# GBE2_PHY.net
KiCad netlist of a schematic drawn in Altium Designer
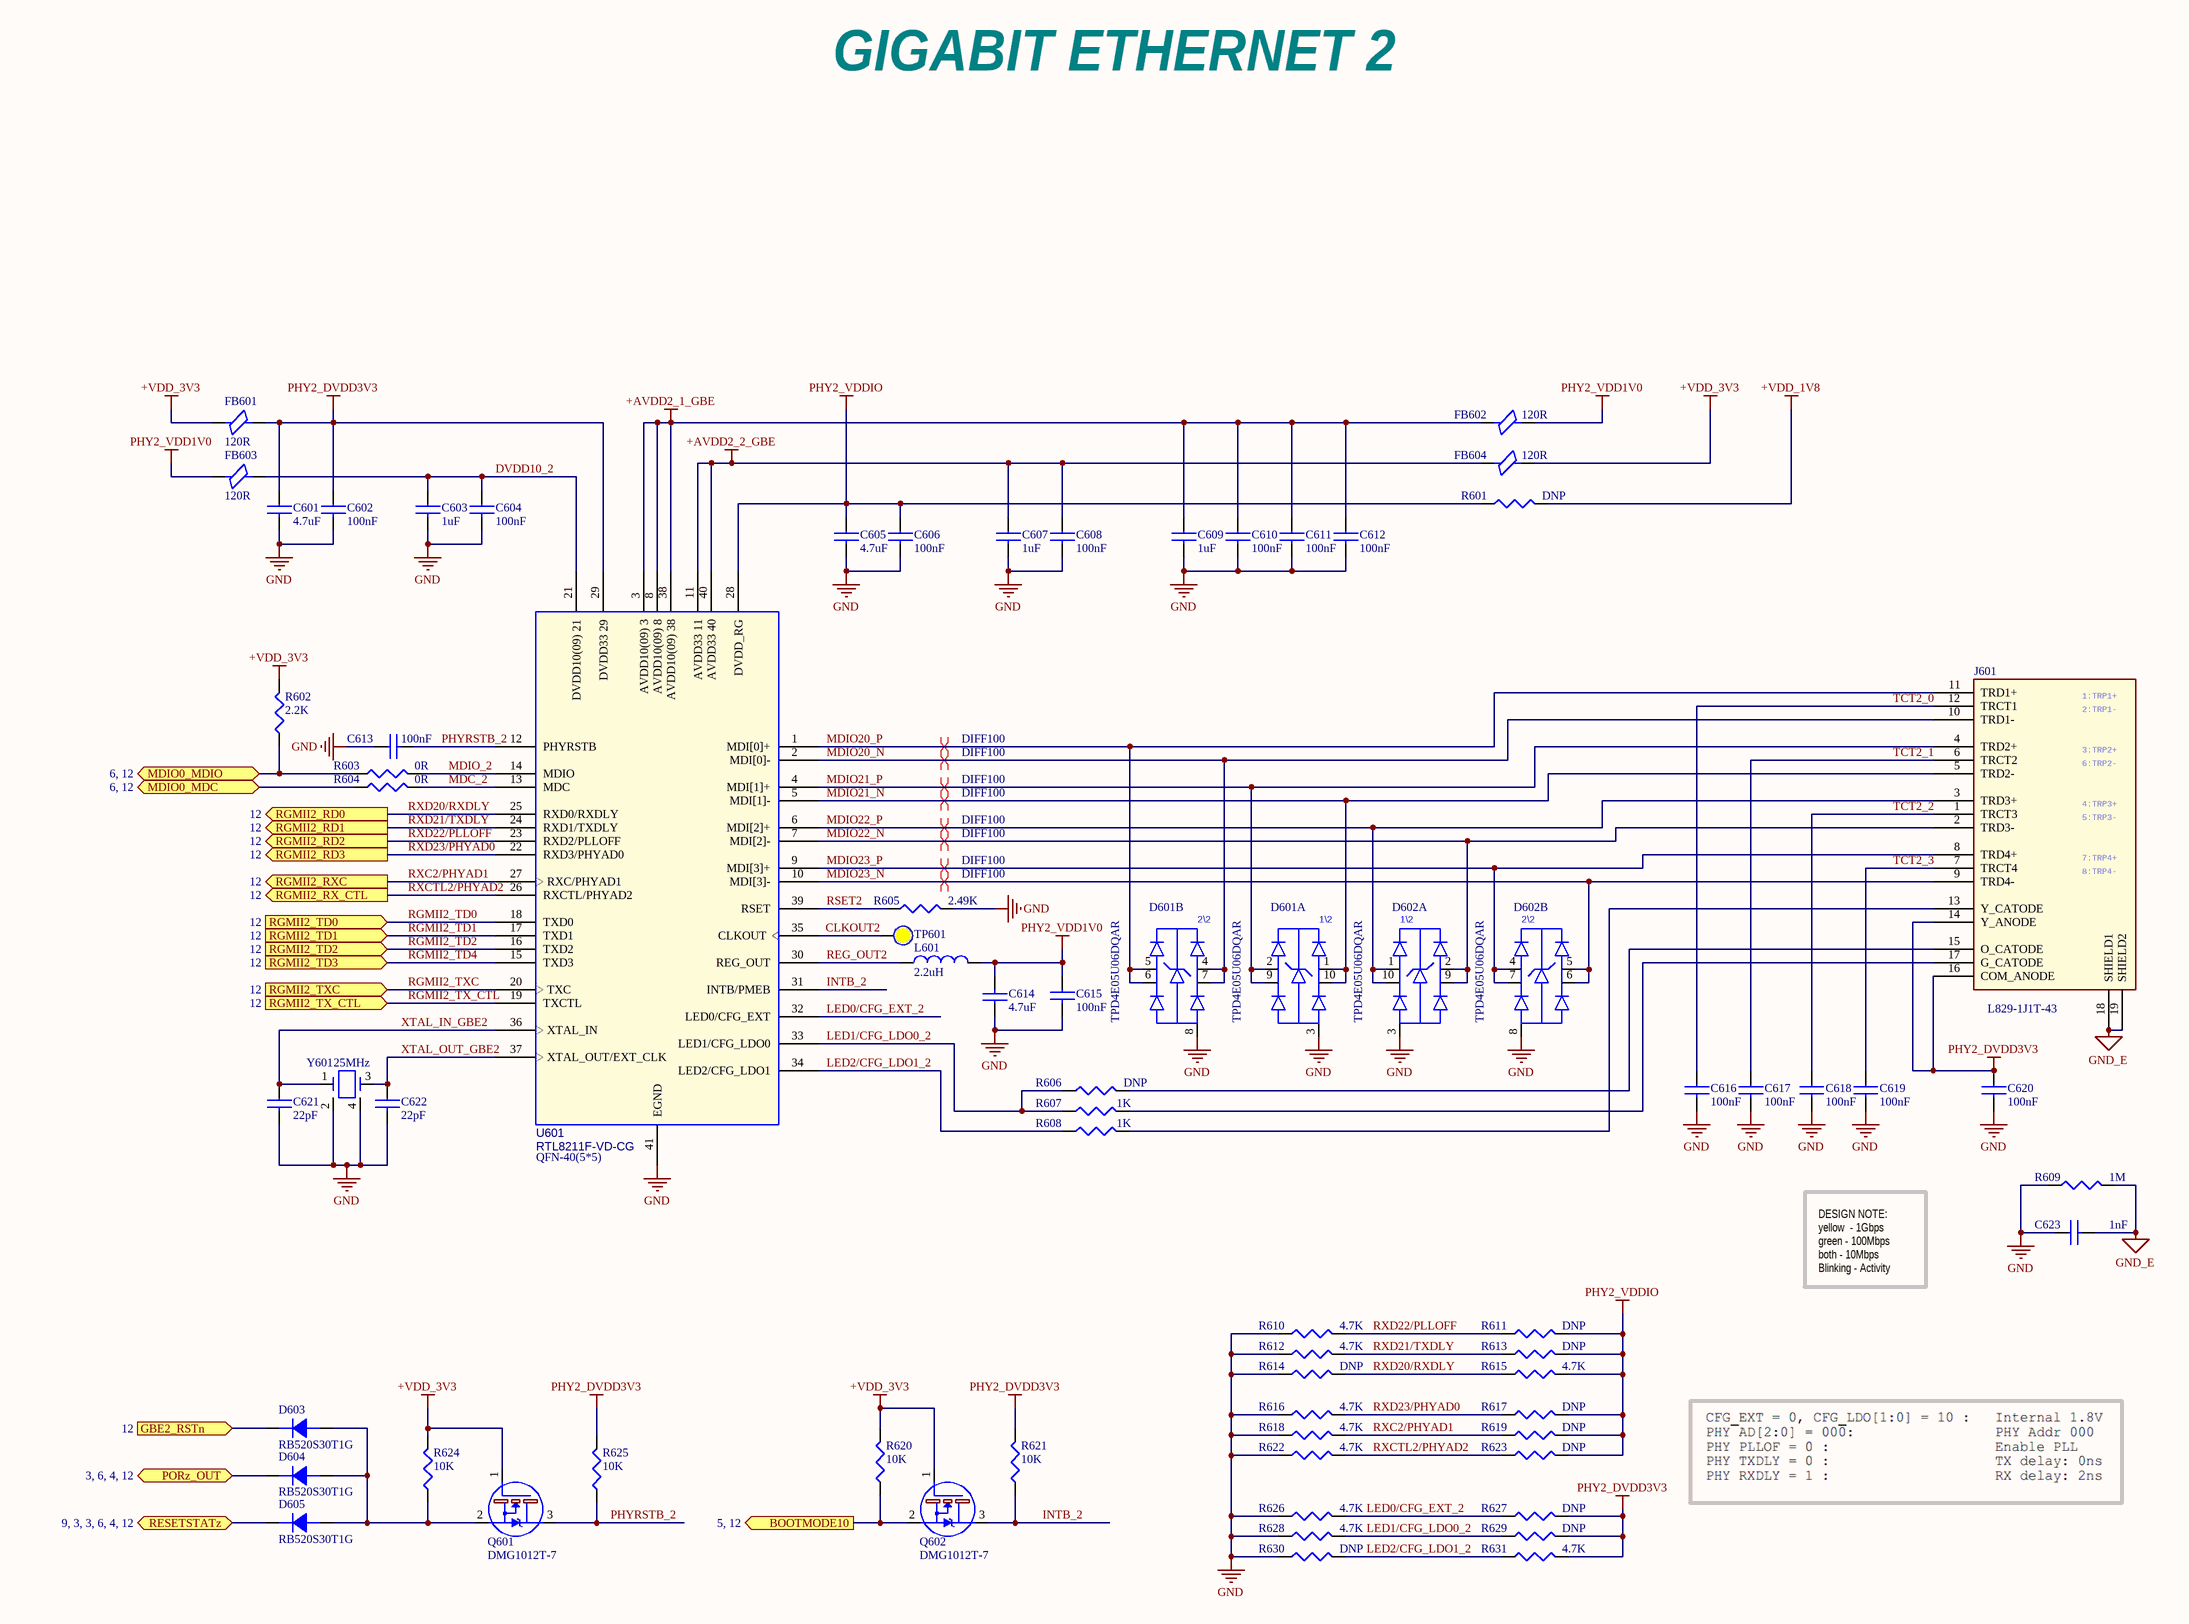
[diagram p0: GBE2 PHY.SchDoc]

(export (version "E")
  (design (tool "Eeschema 10.0.6"))
  (components
    (comp (ref "C601")
      (value "4.7uF")
      (footprint "C0402")
      (description "Multilayer Ceramic Capacitor, 4.7 uF, 6.3V, ± 10%, X5R, 0402 [1005 Metric]")
      (fields
        (field (name "MANUFACTURER") "Yageo")
        (field (name "MANUFACTURER PART NUMBER") "CC0402MRX5R5BB475")
      )
      (libsource (lib "Schlib SOM AM625") (part "CC0402MRX5R5BB475"))
    )
    (comp (ref "C602")
      (value "100nF")
      (footprint "C0201")
      (description "Multilayer Ceramic Capacitor, 0.1 uF, 16 V, ± 10%, X5R, 0201 [0603 Metric]")
      (fields
        (field (name "MANUFACTURER") "Yageo")
        (field (name "MANUFACTURER PART NUMBER") "CC0201KRX5R6BB104")
      )
      (libsource (lib "Schlib SOM AM625") (part "CC0201KRX5R6BB104"))
    )
    (comp (ref "C603")
      (value "1uF")
      (footprint "C0201")
      (description "Multilayer Ceramic Capacitor, 1 uF, 50 V, ± 0.1pF, C0G (NP0), 0201 [1005 Metric]")
      (fields
        (field (name "MANUFACTURER") "Yageo")
        (field (name "MANUFACTURER PART NUMBER") "CC0201MRX5R5BB105")
      )
      (libsource (lib "Schlib SOM AM625") (part "CC0201MRX5R5BB105"))
    )
    (comp (ref "C604")
      (value "100nF")
      (footprint "C0201")
      (description "Multilayer Ceramic Capacitor, 0.1 uF, 16 V, ± 10%, X5R, 0201 [0603 Metric]")
      (fields
        (field (name "MANUFACTURER") "Yageo")
        (field (name "MANUFACTURER PART NUMBER") "CC0201KRX5R6BB104")
      )
      (libsource (lib "Schlib SOM AM625") (part "CC0201KRX5R6BB104"))
    )
    (comp (ref "C605")
      (value "4.7uF")
      (footprint "C0402")
      (description "Multilayer Ceramic Capacitor, 4.7 uF, 6.3V, ± 10%, X5R, 0402 [1005 Metric]")
      (fields
        (field (name "MANUFACTURER") "Yageo")
        (field (name "MANUFACTURER PART NUMBER") "CC0402MRX5R5BB475")
      )
      (libsource (lib "Schlib SOM AM625") (part "CC0402MRX5R5BB475"))
    )
    (comp (ref "C606")
      (value "100nF")
      (footprint "C0201")
      (description "Multilayer Ceramic Capacitor, 0.1 uF, 16 V, ± 10%, X5R, 0201 [0603 Metric]")
      (fields
        (field (name "MANUFACTURER") "Yageo")
        (field (name "MANUFACTURER PART NUMBER") "CC0201KRX5R6BB104")
      )
      (libsource (lib "Schlib SOM AM625") (part "CC0201KRX5R6BB104"))
    )
    (comp (ref "C607")
      (value "1uF")
      (footprint "C0201")
      (description "Multilayer Ceramic Capacitor, 1 uF, 50 V, ± 0.1pF, C0G (NP0), 0201 [1005 Metric]")
      (fields
        (field (name "MANUFACTURER") "Yageo")
        (field (name "MANUFACTURER PART NUMBER") "CC0201MRX5R5BB105")
      )
      (libsource (lib "Schlib SOM AM625") (part "CC0201MRX5R5BB105"))
    )
    (comp (ref "C608")
      (value "100nF")
      (footprint "C0201")
      (description "Multilayer Ceramic Capacitor, 0.1 uF, 16 V, ± 10%, X5R, 0201 [0603 Metric]")
      (fields
        (field (name "MANUFACTURER") "Yageo")
        (field (name "MANUFACTURER PART NUMBER") "CC0201KRX5R6BB104")
      )
      (libsource (lib "Schlib SOM AM625") (part "CC0201KRX5R6BB104"))
    )
    (comp (ref "C609")
      (value "1uF")
      (footprint "C0201")
      (description "Multilayer Ceramic Capacitor, 1 uF, 50 V, ± 0.1pF, C0G (NP0), 0201 [1005 Metric]")
      (fields
        (field (name "MANUFACTURER") "Yageo")
        (field (name "MANUFACTURER PART NUMBER") "CC0201MRX5R5BB105")
      )
      (libsource (lib "Schlib SOM AM625") (part "CC0201MRX5R5BB105"))
    )
    (comp (ref "C610")
      (value "100nF")
      (footprint "C0201")
      (description "Multilayer Ceramic Capacitor, 0.1 uF, 16 V, ± 10%, X5R, 0201 [0603 Metric]")
      (fields
        (field (name "MANUFACTURER") "Yageo")
        (field (name "MANUFACTURER PART NUMBER") "CC0201KRX5R6BB104")
      )
      (libsource (lib "Schlib SOM AM625") (part "CC0201KRX5R6BB104"))
    )
    (comp (ref "C611")
      (value "100nF")
      (footprint "C0201")
      (description "Multilayer Ceramic Capacitor, 0.1 uF, 16 V, ± 10%, X5R, 0201 [0603 Metric]")
      (fields
        (field (name "MANUFACTURER") "Yageo")
        (field (name "MANUFACTURER PART NUMBER") "CC0201KRX5R6BB104")
      )
      (libsource (lib "Schlib SOM AM625") (part "CC0201KRX5R6BB104"))
    )
    (comp (ref "C612")
      (value "100nF")
      (footprint "C0201")
      (description "Multilayer Ceramic Capacitor, 0.1 uF, 16 V, ± 10%, X5R, 0201 [0603 Metric]")
      (fields
        (field (name "MANUFACTURER") "Yageo")
        (field (name "MANUFACTURER PART NUMBER") "CC0201KRX5R6BB104")
      )
      (libsource (lib "Schlib SOM AM625") (part "CC0201KRX5R6BB104"))
    )
    (comp (ref "C613")
      (value "100nF")
      (footprint "C0201")
      (description "Multilayer Ceramic Capacitor, 0.1 uF, 16 V, ± 10%, X5R, 0201 [0603 Metric]")
      (fields
        (field (name "MANUFACTURER") "Yageo")
        (field (name "MANUFACTURER PART NUMBER") "CC0201KRX5R6BB104")
      )
      (libsource (lib "Schlib SOM AM625") (part "CC0201KRX5R6BB104"))
    )
    (comp (ref "C614")
      (value "4.7uF")
      (footprint "C0402")
      (description "Multilayer Ceramic Capacitor, 4.7 uF, 6.3V, ± 10%, X5R, 0402 [1005 Metric]")
      (fields
        (field (name "MANUFACTURER") "Yageo")
        (field (name "MANUFACTURER PART NUMBER") "CC0402MRX5R5BB475")
      )
      (libsource (lib "Schlib SOM AM625") (part "CC0402MRX5R5BB475"))
    )
    (comp (ref "C615")
      (value "100nF")
      (footprint "C0201")
      (description "Multilayer Ceramic Capacitor, 0.1 uF, 16 V, ± 10%, X5R, 0201 [0603 Metric]")
      (fields
        (field (name "MANUFACTURER") "Yageo")
        (field (name "MANUFACTURER PART NUMBER") "CC0201KRX5R6BB104")
      )
      (libsource (lib "Schlib SOM AM625") (part "CC0201KRX5R6BB104"))
    )
    (comp (ref "C616")
      (value "100nF")
      (footprint "C0402")
      (description "Multilayer Ceramic Capacitor, 0.1 uF, 50 V, ± 10%, X5R, 0402 [1005 Metric]")
      (fields
        (field (name "MANUFACTURER") "TDK")
        (field (name "MANUFACTURER PART NUMBER") "C1005X5R1H104K050BB")
      )
      (libsource (lib "Schlib SOM AM625") (part "C1005X5R1H104K050BB"))
    )
    (comp (ref "C617")
      (value "100nF")
      (footprint "C0402")
      (description "Multilayer Ceramic Capacitor, 0.1 uF, 50 V, ± 10%, X5R, 0402 [1005 Metric]")
      (fields
        (field (name "MANUFACTURER") "TDK")
        (field (name "MANUFACTURER PART NUMBER") "C1005X5R1H104K050BB")
      )
      (libsource (lib "Schlib SOM AM625") (part "C1005X5R1H104K050BB"))
    )
    (comp (ref "C618")
      (value "100nF")
      (footprint "C0402")
      (description "Multilayer Ceramic Capacitor, 0.1 uF, 50 V, ± 10%, X5R, 0402 [1005 Metric]")
      (fields
        (field (name "MANUFACTURER") "TDK")
        (field (name "MANUFACTURER PART NUMBER") "C1005X5R1H104K050BB")
      )
      (libsource (lib "Schlib SOM AM625") (part "C1005X5R1H104K050BB"))
    )
    (comp (ref "C619")
      (value "100nF")
      (footprint "C0402")
      (description "Multilayer Ceramic Capacitor, 0.1 uF, 50 V, ± 10%, X5R, 0402 [1005 Metric]")
      (fields
        (field (name "MANUFACTURER") "TDK")
        (field (name "MANUFACTURER PART NUMBER") "C1005X5R1H104K050BB")
      )
      (libsource (lib "Schlib SOM AM625") (part "C1005X5R1H104K050BB"))
    )
    (comp (ref "C620")
      (value "100nF")
      (footprint "C0402")
      (description "Multilayer Ceramic Capacitor, 0.1 uF, 50 V, ± 10%, X5R, 0402 [1005 Metric]")
      (fields
        (field (name "MANUFACTURER") "TDK")
        (field (name "MANUFACTURER PART NUMBER") "C1005X5R1H104K050BB")
      )
      (libsource (lib "Schlib SOM AM625") (part "C1005X5R1H104K050BB"))
    )
    (comp (ref "C621")
      (value "22pF")
      (footprint "C0201")
      (description "0201 22 pF 50 V ±5 % Tolerance NP0 SMT Multilayer Ceramic Capacitor")
      (fields
        (field (name "MANUFACTURER") "Yageo")
        (field (name "MANUFACTURER PART NUMBER") "CC0201JRNPO9BN220")
      )
      (libsource (lib "Schlib SOM AM625") (part "CC0201JRNPO9BN220"))
    )
    (comp (ref "C622")
      (value "22pF")
      (footprint "C0201")
      (description "0201 22 pF 50 V ±5 % Tolerance NP0 SMT Multilayer Ceramic Capacitor")
      (fields
        (field (name "MANUFACTURER") "Yageo")
        (field (name "MANUFACTURER PART NUMBER") "CC0201JRNPO9BN220")
      )
      (libsource (lib "Schlib SOM AM625") (part "CC0201JRNPO9BN220"))
    )
    (comp (ref "C623")
      (value "1nF")
      (footprint "C1206B/3216MM")
      (description "Cap Ceramic 0.001uF 1000V X7R 10% Pad SMD 1206 125°C Low ESR Automotive Medical T/R")
      (fields
        (field (name "MANUFACTURER") "KEMET")
        (field (name "MANUFACTURER PART NUMBER") "C1206C102KDRACAUTO")
      )
      (libsource (lib "Schlib SOM AM625") (part "C1206C102KDRACAUTO"))
    )
    (comp (ref "D601")
      (value "TPD4E05U06DQAR")
      (footprint "10-USON")
      (description "Quad 0.5-pF, 5.5-V, ±12-kV ESD protection diode for USB, HDMI & High Speed Interfaces")
      (fields (field (name "MANUFACTURER") "Texas Instruments"))
      (libsource (lib "Schlib SOM AM625") (part "TPD4E05U06DQAR"))
    )
    (comp (ref "D602")
      (value "TPD4E05U06DQAR")
      (footprint "10-USON")
      (description "Quad 0.5-pF, 5.5-V, ±12-kV ESD protection diode for USB, HDMI & High Speed Interfaces")
      (fields (field (name "MANUFACTURER") "Texas Instruments"))
      (libsource (lib "Schlib SOM AM625") (part "TPD4E05U06DQAR"))
    )
    (comp (ref "D603")
      (value "RB520S30T1G")
      (footprint "sod_523")
      (description "Diode Schottky 30V 0.2A 2-Pin SOD-523 T/R - Product that comes on tape, but is not reeled")
      (fields (field (name "MANUFACTURER") "ON Semiconductor"))
      (libsource (lib "Schlib SOM AM625") (part "RB520S30T1G"))
    )
    (comp (ref "D604")
      (value "RB520S30T1G")
      (footprint "sod_523")
      (description "Diode Schottky 30V 0.2A 2-Pin SOD-523 T/R - Product that comes on tape, but is not reeled")
      (fields (field (name "MANUFACTURER") "ON Semiconductor"))
      (libsource (lib "Schlib SOM AM625") (part "RB520S30T1G"))
    )
    (comp (ref "D605")
      (value "RB520S30T1G")
      (footprint "sod_523")
      (description "Diode Schottky 30V 0.2A 2-Pin SOD-523 T/R - Product that comes on tape, but is not reeled")
      (fields (field (name "MANUFACTURER") "ON Semiconductor"))
      (libsource (lib "Schlib SOM AM625") (part "RB520S30T1G"))
    )
    (comp (ref "FB601")
      (value "120R")
      (footprint "FB0402")
      (description "Ferrite Beads Multi-Layer 120Ohm 25% 100MHz 1.3A 0.09Ohm DCR 0402 Automotive T/R")
      (fields
        (field (name "MANUFACTURER") "Murata")
        (field (name "MANUFACTURER PART NUMBER") "BLM15PD121SZ1D")
      )
      (libsource (lib "Schlib SOM AM625") (part "BLM15PD121SZ1D"))
    )
    (comp (ref "FB602")
      (value "120R")
      (footprint "FB0402")
      (description "Ferrite Beads Multi-Layer 120Ohm 25% 100MHz 1.3A 0.09Ohm DCR 0402 Automotive T/R")
      (fields
        (field (name "MANUFACTURER") "Murata")
        (field (name "MANUFACTURER PART NUMBER") "BLM15PD121SZ1D")
      )
      (libsource (lib "Schlib SOM AM625") (part "BLM15PD121SZ1D"))
    )
    (comp (ref "FB603")
      (value "120R")
      (footprint "FB0402")
      (description "Ferrite Beads Multi-Layer 120Ohm 25% 100MHz 1.3A 0.09Ohm DCR 0402 Automotive T/R")
      (fields
        (field (name "MANUFACTURER") "Murata")
        (field (name "MANUFACTURER PART NUMBER") "BLM15PD121SZ1D")
      )
      (libsource (lib "Schlib SOM AM625") (part "BLM15PD121SZ1D"))
    )
    (comp (ref "FB604")
      (value "120R")
      (footprint "FB0402")
      (description "Ferrite Beads Multi-Layer 120Ohm 25% 100MHz 1.3A 0.09Ohm DCR 0402 Automotive T/R")
      (fields
        (field (name "MANUFACTURER") "Murata")
        (field (name "MANUFACTURER PART NUMBER") "BLM15PD121SZ1D")
      )
      (libsource (lib "Schlib SOM AM625") (part "BLM15PD121SZ1D"))
    )
    (comp (ref "J601")
      (value "L829-1J1T-43")
      (footprint "L829-1J1T-43")
      (description "CONN MAGJACK 1PORT SHLD 1000BT")
      (fields
        (field (name "MANUFACTURER") "Bel Fuse Inc")
        (field (name ".CHECKED PCB") "RF")
        (field (name ".CHECKED SCH") "RF")
      )
      (libsource (lib "Schlib SOM AM625") (part "L829-1J1T-43"))
    )
    (comp (ref "L601")
      (value "2.2uH")
      (footprint "l2016")
      (description "Inductor Power Shielded Wirewound 2.2uH 20% 1MHz Metal 1.4A 0.168Ohm DCR 0806 T/R")
      (fields
        (field (name "MANUFACTURER") "Murata")
        (field (name "MANUFACTURER PART NUMBER") "DFE201610P-2R2M=P2")
      )
      (libsource (lib "Schlib SOM AM625") (part "DFE201610P-2R2M=P2"))
    )
    (comp (ref "Q601")
      (value "DMG1012T-7")
      (footprint "sot_523")
      (description "Transistor MOSFET NTR4003NT1G, SOT23, ON Semi")
      (fields (field (name "MANUFACTURER") "Diodes"))
      (libsource (lib "Schlib SOM AM625") (part "DMG1012T-7"))
    )
    (comp (ref "Q602")
      (value "DMG1012T-7")
      (footprint "sot_523")
      (description "Transistor MOSFET NTR4003NT1G, SOT23, ON Semi")
      (fields (field (name "MANUFACTURER") "Diodes"))
      (libsource (lib "Schlib SOM AM625") (part "DMG1012T-7"))
    )
    (comp (ref "R601")
      (value "DNP")
      (footprint "R0402")
      (description "Zero Ohm Resistor, Jumper, 0402 [1005 Metric], Thick Film, 63 mW, 1 A, Surface Mount")
      (fields
        (field (name "MANUFACTURER") "Yageo")
        (field (name "MANUFACTURER PART NUMBER") "RC0402JR-070RL")
      )
      (libsource (lib "Schlib SOM AM625") (part "RC0402JR-070RL"))
    )
    (comp (ref "R602")
      (value "2.2K")
      (footprint "R0201")
      (description "SMD Chip Resistor, 2.2 kOhm, ± 1%, 50 mW, 0201 [0603 Metric], Thick Film, General Purpose")
      (fields
        (field (name "MANUFACTURER") "Yageo")
        (field (name "MANUFACTURER PART NUMBER") "RC0201FR-072K2L")
      )
      (libsource (lib "Schlib SOM AM625") (part "RC0201FR-072K2L"))
    )
    (comp (ref "R603")
      (value "0R")
      (footprint "R0201")
      (description "Zero Ohm Resistor, Jumper, 0201 [0603 Metric], Thick Film, 50 mW, 500 mA, Surface Mount")
      (fields
        (field (name "MANUFACTURER") "Yageo")
        (field (name "MANUFACTURER PART NUMBER") "RC0201JR-070RL")
      )
      (libsource (lib "Schlib SOM AM625") (part "RC0201JR-070RL"))
    )
    (comp (ref "R604")
      (value "0R")
      (footprint "R0201")
      (description "Zero Ohm Resistor, Jumper, 0201 [0603 Metric], Thick Film, 50 mW, 500 mA, Surface Mount")
      (fields
        (field (name "MANUFACTURER") "Yageo")
        (field (name "MANUFACTURER PART NUMBER") "RC0201JR-070RL")
      )
      (libsource (lib "Schlib SOM AM625") (part "RC0201JR-070RL"))
    )
    (comp (ref "R605")
      (value "2.49K")
      (footprint "R0201")
      (description "SMD Chip Resistor, 2.49 kOhm, ± 1%, 50 mW, 0201 [0603 Metric], Thick Film, General Purpose")
      (fields
        (field (name "MANUFACTURER") "Yageo")
        (field (name "MANUFACTURER PART NUMBER") "RC0201FR-072K49L")
      )
      (libsource (lib "Schlib SOM AM625") (part "RC0201FR-072K49L"))
    )
    (comp (ref "R606")
      (value "DNP")
      (footprint "R0402")
      (description "Zero Ohm Resistor, Jumper, 0402 [1005 Metric], Thick Film, 63 mW, 1 A, Surface Mount")
      (fields
        (field (name "MANUFACTURER") "Yageo")
        (field (name "MANUFACTURER PART NUMBER") "RC0402JR-070RL")
      )
      (libsource (lib "Schlib SOM AM625") (part "RC0402JR-070RL"))
    )
    (comp (ref "R607")
      (value "1K")
      (footprint "R0402")
      (description "SMD Chip Resistor, 1 kOhm, ± 1%, 63 mW, 0402 [1005 Metric], Thick Film, General Purpose")
      (fields
        (field (name "MANUFACTURER") "Yageo")
        (field (name "MANUFACTURER PART NUMBER") "RC0402FR-071KL")
      )
      (libsource (lib "Schlib SOM AM625") (part "RC0402FR-071KL"))
    )
    (comp (ref "R608")
      (value "1K")
      (footprint "R0402")
      (description "SMD Chip Resistor, 1 kOhm, ± 1%, 63 mW, 0402 [1005 Metric], Thick Film, General Purpose")
      (fields
        (field (name "MANUFACTURER") "Yageo")
        (field (name "MANUFACTURER PART NUMBER") "RC0402FR-071KL")
      )
      (libsource (lib "Schlib SOM AM625") (part "RC0402FR-071KL"))
    )
    (comp (ref "R609")
      (value "1M")
      (footprint "R1206B/3216MM")
      (description "SMD Chip Resistor, 1 MOhm, ± 1%, 250 mW, 1206 [3216 Metric], Thick Film, General Purpose")
      (fields
        (field (name "MANUFACTURER") "Yageo")
        (field (name "MANUFACTURER PART NUMBER") "RC1206FR-071ML")
      )
      (libsource (lib "Schlib SOM AM625") (part "RC1206FR-071ML"))
    )
    (comp (ref "R610")
      (value "4.7K")
      (footprint "R0201")
      (description "SMD Chip Resistor, 4.7 kOhm, ± 5%, 50 mW, 0201 [0603 Metric], Thick Film, General Purpose")
      (fields
        (field (name "MANUFACTURER") "Yageo")
        (field (name "MANUFACTURER PART NUMBER") "RC0201JR-074K7L")
      )
      (libsource (lib "Schlib SOM AM625") (part "RC0201JR-074K7L"))
    )
    (comp (ref "R611")
      (value "DNP")
      (footprint "R0201")
      (description "SMD Chip Resistor, 4.7 kOhm, ± 5%, 50 mW, 0201 [0603 Metric], Thick Film, General Purpose")
      (fields
        (field (name "MANUFACTURER") "Yageo")
        (field (name "MANUFACTURER PART NUMBER") "RC0201JR-074K7L")
      )
      (libsource (lib "Schlib SOM AM625") (part "RC0201JR-074K7L"))
    )
    (comp (ref "R612")
      (value "4.7K")
      (footprint "R0201")
      (description "SMD Chip Resistor, 4.7 kOhm, ± 5%, 50 mW, 0201 [0603 Metric], Thick Film, General Purpose")
      (fields
        (field (name "MANUFACTURER") "Yageo")
        (field (name "MANUFACTURER PART NUMBER") "RC0201JR-074K7L")
      )
      (libsource (lib "Schlib SOM AM625") (part "RC0201JR-074K7L"))
    )
    (comp (ref "R613")
      (value "DNP")
      (footprint "R0201")
      (description "SMD Chip Resistor, 4.7 kOhm, ± 5%, 50 mW, 0201 [0603 Metric], Thick Film, General Purpose")
      (fields
        (field (name "MANUFACTURER") "Yageo")
        (field (name "MANUFACTURER PART NUMBER") "RC0201JR-074K7L")
      )
      (libsource (lib "Schlib SOM AM625") (part "RC0201JR-074K7L"))
    )
    (comp (ref "R614")
      (value "DNP")
      (footprint "R0201")
      (description "SMD Chip Resistor, 4.7 kOhm, ± 5%, 50 mW, 0201 [0603 Metric], Thick Film, General Purpose")
      (fields
        (field (name "MANUFACTURER") "Yageo")
        (field (name "MANUFACTURER PART NUMBER") "RC0201JR-074K7L")
      )
      (libsource (lib "Schlib SOM AM625") (part "RC0201JR-074K7L"))
    )
    (comp (ref "R615")
      (value "4.7K")
      (footprint "R0201")
      (description "SMD Chip Resistor, 4.7 kOhm, ± 5%, 50 mW, 0201 [0603 Metric], Thick Film, General Purpose")
      (fields
        (field (name "MANUFACTURER") "Yageo")
        (field (name "MANUFACTURER PART NUMBER") "RC0201JR-074K7L")
      )
      (libsource (lib "Schlib SOM AM625") (part "RC0201JR-074K7L"))
    )
    (comp (ref "R616")
      (value "4.7K")
      (footprint "R0201")
      (description "SMD Chip Resistor, 4.7 kOhm, ± 5%, 50 mW, 0201 [0603 Metric], Thick Film, General Purpose")
      (fields
        (field (name "MANUFACTURER") "Yageo")
        (field (name "MANUFACTURER PART NUMBER") "RC0201JR-074K7L")
      )
      (libsource (lib "Schlib SOM AM625") (part "RC0201JR-074K7L"))
    )
    (comp (ref "R617")
      (value "DNP")
      (footprint "R0201")
      (description "SMD Chip Resistor, 4.7 kOhm, ± 5%, 50 mW, 0201 [0603 Metric], Thick Film, General Purpose")
      (fields
        (field (name "MANUFACTURER") "Yageo")
        (field (name "MANUFACTURER PART NUMBER") "RC0201JR-074K7L")
      )
      (libsource (lib "Schlib SOM AM625") (part "RC0201JR-074K7L"))
    )
    (comp (ref "R618")
      (value "4.7K")
      (footprint "R0201")
      (description "SMD Chip Resistor, 4.7 kOhm, ± 5%, 50 mW, 0201 [0603 Metric], Thick Film, General Purpose")
      (fields
        (field (name "MANUFACTURER") "Yageo")
        (field (name "MANUFACTURER PART NUMBER") "RC0201JR-074K7L")
      )
      (libsource (lib "Schlib SOM AM625") (part "RC0201JR-074K7L"))
    )
    (comp (ref "R619")
      (value "DNP")
      (footprint "R0201")
      (description "SMD Chip Resistor, 4.7 kOhm, ± 5%, 50 mW, 0201 [0603 Metric], Thick Film, General Purpose")
      (fields
        (field (name "MANUFACTURER") "Yageo")
        (field (name "MANUFACTURER PART NUMBER") "RC0201JR-074K7L")
      )
      (libsource (lib "Schlib SOM AM625") (part "RC0201JR-074K7L"))
    )
    (comp (ref "R620")
      (value "10K")
      (footprint "R0201")
      (description "SMD Chip Resistor, 10 kOhm, ± 1%, 50 mW, 0201 [0603 Metric], Thick Film, General Purpose")
      (fields
        (field (name "MANUFACTURER") "Yageo")
        (field (name "MANUFACTURER PART NUMBER") "RC0201FR-0710KL")
      )
      (libsource (lib "Schlib SOM AM625") (part "RC0201FR-0710KL"))
    )
    (comp (ref "R621")
      (value "10K")
      (footprint "R0201")
      (description "SMD Chip Resistor, 10 kOhm, ± 1%, 50 mW, 0201 [0603 Metric], Thick Film, General Purpose")
      (fields
        (field (name "MANUFACTURER") "Yageo")
        (field (name "MANUFACTURER PART NUMBER") "RC0201FR-0710KL")
      )
      (libsource (lib "Schlib SOM AM625") (part "RC0201FR-0710KL"))
    )
    (comp (ref "R622")
      (value "4.7K")
      (footprint "R0201")
      (description "SMD Chip Resistor, 4.7 kOhm, ± 5%, 50 mW, 0201 [0603 Metric], Thick Film, General Purpose")
      (fields
        (field (name "MANUFACTURER") "Yageo")
        (field (name "MANUFACTURER PART NUMBER") "RC0201JR-074K7L")
      )
      (libsource (lib "Schlib SOM AM625") (part "RC0201JR-074K7L"))
    )
    (comp (ref "R623")
      (value "DNP")
      (footprint "R0201")
      (description "SMD Chip Resistor, 4.7 kOhm, ± 5%, 50 mW, 0201 [0603 Metric], Thick Film, General Purpose")
      (fields
        (field (name "MANUFACTURER") "Yageo")
        (field (name "MANUFACTURER PART NUMBER") "RC0201JR-074K7L")
      )
      (libsource (lib "Schlib SOM AM625") (part "RC0201JR-074K7L"))
    )
    (comp (ref "R624")
      (value "10K")
      (footprint "R0201")
      (description "SMD Chip Resistor, 10 kOhm, ± 1%, 50 mW, 0201 [0603 Metric], Thick Film, General Purpose")
      (fields
        (field (name "MANUFACTURER") "Yageo")
        (field (name "MANUFACTURER PART NUMBER") "RC0201FR-0710KL")
      )
      (libsource (lib "Schlib SOM AM625") (part "RC0201FR-0710KL"))
    )
    (comp (ref "R625")
      (value "10K")
      (footprint "R0201")
      (description "SMD Chip Resistor, 10 kOhm, ± 1%, 50 mW, 0201 [0603 Metric], Thick Film, General Purpose")
      (fields
        (field (name "MANUFACTURER") "Yageo")
        (field (name "MANUFACTURER PART NUMBER") "RC0201FR-0710KL")
      )
      (libsource (lib "Schlib SOM AM625") (part "RC0201FR-0710KL"))
    )
    (comp (ref "R626")
      (value "4.7K")
      (footprint "R0201")
      (description "SMD Chip Resistor, 4.7 kOhm, ± 5%, 50 mW, 0201 [0603 Metric], Thick Film, General Purpose")
      (fields
        (field (name "MANUFACTURER") "Yageo")
        (field (name "MANUFACTURER PART NUMBER") "RC0201JR-074K7L")
      )
      (libsource (lib "Schlib SOM AM625") (part "RC0201JR-074K7L"))
    )
    (comp (ref "R627")
      (value "DNP")
      (footprint "R0201")
      (description "SMD Chip Resistor, 4.7 kOhm, ± 5%, 50 mW, 0201 [0603 Metric], Thick Film, General Purpose")
      (fields
        (field (name "MANUFACTURER") "Yageo")
        (field (name "MANUFACTURER PART NUMBER") "RC0201JR-074K7L")
      )
      (libsource (lib "Schlib SOM AM625") (part "RC0201JR-074K7L"))
    )
    (comp (ref "R628")
      (value "4.7K")
      (footprint "R0201")
      (description "SMD Chip Resistor, 4.7 kOhm, ± 5%, 50 mW, 0201 [0603 Metric], Thick Film, General Purpose")
      (fields
        (field (name "MANUFACTURER") "Yageo")
        (field (name "MANUFACTURER PART NUMBER") "RC0201JR-074K7L")
      )
      (libsource (lib "Schlib SOM AM625") (part "RC0201JR-074K7L"))
    )
    (comp (ref "R629")
      (value "DNP")
      (footprint "R0201")
      (description "SMD Chip Resistor, 4.7 kOhm, ± 5%, 50 mW, 0201 [0603 Metric], Thick Film, General Purpose")
      (fields
        (field (name "MANUFACTURER") "Yageo")
        (field (name "MANUFACTURER PART NUMBER") "RC0201JR-074K7L")
      )
      (libsource (lib "Schlib SOM AM625") (part "RC0201JR-074K7L"))
    )
    (comp (ref "R630")
      (value "DNP")
      (footprint "R0201")
      (description "SMD Chip Resistor, 4.7 kOhm, ± 5%, 50 mW, 0201 [0603 Metric], Thick Film, General Purpose")
      (fields
        (field (name "MANUFACTURER") "Yageo")
        (field (name "MANUFACTURER PART NUMBER") "RC0201JR-074K7L")
      )
      (libsource (lib "Schlib SOM AM625") (part "RC0201JR-074K7L"))
    )
    (comp (ref "R631")
      (value "4.7K")
      (footprint "R0201")
      (description "SMD Chip Resistor, 4.7 kOhm, ± 5%, 50 mW, 0201 [0603 Metric], Thick Film, General Purpose")
      (fields
        (field (name "MANUFACTURER") "Yageo")
        (field (name "MANUFACTURER PART NUMBER") "RC0201JR-074K7L")
      )
      (libsource (lib "Schlib SOM AM625") (part "RC0201JR-074K7L"))
    )
    (comp (ref "TP601")
      (value "~")
      (footprint "Test Point 1 MM")
      (description "Test Point")
      (libsource (lib "BYTECH_HW_LIB_2019") (part "Test Point"))
    )
    (comp (ref "U601")
      (value "RTL8211F-VD-CG")
      (footprint "qfn40_0D4_5x5mm")
      (description "IC, Interface, Ethernet, RTL8211F-VD-CG, QFN-40(5*5)")
      (fields
        (field (name "MANUFACTURER") "Realtek")
        (field (name "PACKAGE SIZE") "QFN-40(5*5)")
        (field (name "Comment") "RTL8211")
      )
      (libsource (lib "Schlib SOM AM625") (part "RTL8211"))
    )
    (comp (ref "Y601")
      (value "25MHz")
      (footprint "x4-smd-3_2x2_5x1_0mm")
      (description "Crystal, 25MHZ, 18PF, SMD")
      (fields (field (name "MANUFACTURER") "IQD") (field (name "MANUFACTURER PART NUMBER") "LFXTAL055299"))
      (libsource (lib "Schlib SOM AM625") (part "LFXTAL055299"))
    )
  )
  (nets
    (net (code "1") (name "+AVDD2_1_GBE") (class "Default")
      (node (ref "C609") (pin "1") (pinfunction "1_1") (pintype "passive"))
      (node (ref "C610") (pin "1") (pinfunction "1_1") (pintype "passive"))
      (node (ref "C611") (pin "1") (pinfunction "1_1") (pintype "passive"))
      (node (ref "C612") (pin "1") (pinfunction "1_1") (pintype "passive"))
      (node (ref "FB602") (pin "1") (pinfunction "1_1") (pintype "passive"))
      (node (ref "U601") (pin "3") (pinfunction "AVDD10(09)_3_3") (pintype "power_in"))
      (node (ref "U601") (pin "38") (pinfunction "AVDD10(09)_38_38") (pintype "power_in"))
      (node (ref "U601") (pin "8") (pinfunction "AVDD10(09)_8_8") (pintype "power_in"))
    )
    (net (code "2") (name "+AVDD2_2_GBE") (class "Default")
      (node (ref "C607") (pin "1") (pinfunction "1_1") (pintype "passive"))
      (node (ref "C608") (pin "1") (pinfunction "1_1") (pintype "passive"))
      (node (ref "FB604") (pin "1") (pinfunction "1_1") (pintype "passive"))
      (node (ref "U601") (pin "11") (pinfunction "AVDD33_11_11") (pintype "power_in"))
      (node (ref "U601") (pin "40") (pinfunction "AVDD33_40_40") (pintype "power_in"))
    )
    (net (code "3") (name "+VDD_1V8") (class "Default")
      (node (ref "R601") (pin "2") (pinfunction "2_2") (pintype "passive"))
    )
    (net (code "4") (name "+VDD_3V3") (class "Default")
      (node (ref "FB601") (pin "1") (pinfunction "1_1") (pintype "passive"))
      (node (ref "FB604") (pin "2") (pinfunction "2_2") (pintype "passive"))
      (node (ref "Q601") (pin "1") (pinfunction "G_1") (pintype "passive"))
      (node (ref "Q602") (pin "1") (pinfunction "G_1") (pintype "passive"))
      (node (ref "R602") (pin "2") (pinfunction "2_2") (pintype "passive"))
      (node (ref "R620") (pin "2") (pinfunction "2_2") (pintype "passive"))
      (node (ref "R624") (pin "2") (pinfunction "2_2") (pintype "passive"))
    )
    (net (code "5") (name "/BOOTMODE10") (class "Default")
      (node (ref "Q602") (pin "2") (pinfunction "S_2") (pintype "passive"))
      (node (ref "R620") (pin "1") (pinfunction "1_1") (pintype "passive"))
    )
    (net (code "6") (name "/CLKOUT2") (class "Default")
      (node (ref "TP601") (pin "0") (pinfunction "0_0") (pintype "passive"))
      (node (ref "U601") (pin "35") (pinfunction "CLKOUT_35") (pintype "passive"))
    )
    (net (code "7") (name "/DVDD10_2") (class "Default")
      (node (ref "C603") (pin "1") (pinfunction "1_1") (pintype "passive"))
      (node (ref "C604") (pin "1") (pinfunction "1_1") (pintype "passive"))
      (node (ref "FB603") (pin "2") (pinfunction "2_2") (pintype "passive"))
      (node (ref "U601") (pin "21") (pinfunction "DVDD10(09)_21_21") (pintype "power_in"))
    )
    (net (code "8") (name "/GBE2_RSTn") (class "Default")
      (node (ref "D603") (pin "2") (pinfunction "C_2") (pintype "passive"))
    )
    (net (code "9") (name "/INTB_2") (class "Default")
      (node (ref "Q602") (pin "3") (pinfunction "D_3") (pintype "passive"))
      (node (ref "R621") (pin "1") (pinfunction "1_1") (pintype "passive"))
      (node (ref "U601") (pin "31") (pinfunction "INTB/PMEB_31") (pintype "passive"))
    )
    (net (code "10") (name "/LED0{slash}CFG_EXT_2") (class "Default")
      (node (ref "R626") (pin "2") (pinfunction "2_2") (pintype "passive"))
      (node (ref "R627") (pin "1") (pinfunction "1_1") (pintype "passive"))
      (node (ref "U601") (pin "32") (pinfunction "LED0/CFG_EXT_32") (pintype "passive"))
    )
    (net (code "11") (name "/LED1{slash}CFG_LDO0_2") (class "Default")
      (node (ref "R606") (pin "1") (pinfunction "1_1") (pintype "passive"))
      (node (ref "R607") (pin "1") (pinfunction "1_1") (pintype "passive"))
      (node (ref "R628") (pin "2") (pinfunction "2_2") (pintype "passive"))
      (node (ref "R629") (pin "1") (pinfunction "1_1") (pintype "passive"))
      (node (ref "U601") (pin "33") (pinfunction "LED1/CFG_LDO0_33") (pintype "passive"))
    )
    (net (code "12") (name "/LED2{slash}CFG_LDO1_2") (class "Default")
      (node (ref "R608") (pin "1") (pinfunction "1_1") (pintype "passive"))
      (node (ref "R630") (pin "2") (pinfunction "2_2") (pintype "passive"))
      (node (ref "R631") (pin "1") (pinfunction "1_1") (pintype "passive"))
      (node (ref "U601") (pin "34") (pinfunction "LED2/CFG_LDO1_34") (pintype "passive"))
    )
    (net (code "13") (name "/MDC_2") (class "Default")
      (node (ref "R604") (pin "2") (pinfunction "2_2") (pintype "passive"))
      (node (ref "U601") (pin "13") (pinfunction "MDC_13") (pintype "passive"))
    )
    (net (code "14") (name "/MDIO0_MDC") (class "Default")
      (node (ref "R604") (pin "1") (pinfunction "1_1") (pintype "passive"))
    )
    (net (code "15") (name "/MDIO0_MDIO") (class "Default")
      (node (ref "R602") (pin "1") (pinfunction "1_1") (pintype "passive"))
      (node (ref "R603") (pin "1") (pinfunction "1_1") (pintype "passive"))
    )
    (net (code "16") (name "/MDIO20_N") (class "Default")
      (node (ref "D601") (pin "4") (pinfunction "3A_4") (pintype "passive"))
      (node (ref "D601") (pin "7") (pinfunction "3B_7") (pintype "passive"))
      (node (ref "J601") (pin "10") (pinfunction "TRD1-_10") (pintype "passive"))
      (node (ref "U601") (pin "2") (pinfunction "MDI[0]-_2") (pintype "passive"))
    )
    (net (code "17") (name "/MDIO20_P") (class "Default")
      (node (ref "D601") (pin "5") (pinfunction "4A_5") (pintype "passive"))
      (node (ref "D601") (pin "6") (pinfunction "4B_6") (pintype "passive"))
      (node (ref "J601") (pin "11") (pinfunction "TRD1+_11") (pintype "passive"))
      (node (ref "U601") (pin "1") (pinfunction "MDI[0]+_1") (pintype "passive"))
    )
    (net (code "18") (name "/MDIO21_N") (class "Default")
      (node (ref "D601") (pin "1") (pinfunction "1A_1") (pintype "passive"))
      (node (ref "D601") (pin "10") (pinfunction "1B_10") (pintype "passive"))
      (node (ref "J601") (pin "5") (pinfunction "TRD2-_5") (pintype "passive"))
      (node (ref "U601") (pin "5") (pinfunction "MDI[1]-_5") (pintype "passive"))
    )
    (net (code "19") (name "/MDIO21_P") (class "Default")
      (node (ref "D601") (pin "2") (pinfunction "2A_2") (pintype "passive"))
      (node (ref "D601") (pin "9") (pinfunction "2B_9") (pintype "passive"))
      (node (ref "J601") (pin "4") (pinfunction "TRD2+_4") (pintype "passive"))
      (node (ref "U601") (pin "4") (pinfunction "MDI[1]+_4") (pintype "passive"))
    )
    (net (code "20") (name "/MDIO22_N") (class "Default")
      (node (ref "D602") (pin "2") (pinfunction "2A_2") (pintype "passive"))
      (node (ref "D602") (pin "9") (pinfunction "2B_9") (pintype "passive"))
      (node (ref "J601") (pin "2") (pinfunction "TRD3-_2") (pintype "passive"))
      (node (ref "U601") (pin "7") (pinfunction "MDI[2]-_7") (pintype "passive"))
    )
    (net (code "21") (name "/MDIO22_P") (class "Default")
      (node (ref "D602") (pin "1") (pinfunction "1A_1") (pintype "passive"))
      (node (ref "D602") (pin "10") (pinfunction "1B_10") (pintype "passive"))
      (node (ref "J601") (pin "3") (pinfunction "TRD3+_3") (pintype "passive"))
      (node (ref "U601") (pin "6") (pinfunction "MDI[2]+_6") (pintype "passive"))
    )
    (net (code "22") (name "/MDIO23_N") (class "Default")
      (node (ref "D602") (pin "5") (pinfunction "4A_5") (pintype "passive"))
      (node (ref "D602") (pin "6") (pinfunction "4B_6") (pintype "passive"))
      (node (ref "J601") (pin "9") (pinfunction "TRD4-_9") (pintype "passive"))
      (node (ref "U601") (pin "10") (pinfunction "MDI[3]-_10") (pintype "passive"))
    )
    (net (code "23") (name "/MDIO23_P") (class "Default")
      (node (ref "D602") (pin "4") (pinfunction "3A_4") (pintype "passive"))
      (node (ref "D602") (pin "7") (pinfunction "3B_7") (pintype "passive"))
      (node (ref "J601") (pin "8") (pinfunction "TRD4+_8") (pintype "passive"))
      (node (ref "U601") (pin "9") (pinfunction "MDI[3]+_9") (pintype "passive"))
    )
    (net (code "24") (name "/MDIO_2") (class "Default")
      (node (ref "R603") (pin "2") (pinfunction "2_2") (pintype "passive"))
      (node (ref "U601") (pin "14") (pinfunction "MDIO_14") (pintype "passive"))
    )
    (net (code "25") (name "/PHYRSTB_2") (class "Default")
      (node (ref "C613") (pin "2") (pinfunction "2_2") (pintype "passive"))
      (node (ref "Q601") (pin "3") (pinfunction "D_3") (pintype "passive"))
      (node (ref "R625") (pin "1") (pinfunction "1_1") (pintype "passive"))
      (node (ref "U601") (pin "12") (pinfunction "PHYRSTB_12") (pintype "passive"))
    )
    (net (code "26") (name "/PORz_OUT") (class "Default")
      (node (ref "D604") (pin "2") (pinfunction "C_2") (pintype "passive"))
    )
    (net (code "27") (name "/REG_OUT2") (class "Default")
      (node (ref "L601") (pin "1") (pinfunction "1_1") (pintype "passive"))
      (node (ref "U601") (pin "30") (pinfunction "REG_OUT_30") (pintype "power_in"))
    )
    (net (code "28") (name "/RESETSTATz") (class "Default")
      (node (ref "D605") (pin "2") (pinfunction "C_2") (pintype "passive"))
    )
    (net (code "29") (name "/RGMII2_TD0") (class "Default")
      (node (ref "U601") (pin "18") (pinfunction "TXD0_18") (pintype "passive"))
    )
    (net (code "30") (name "/RGMII2_TD1") (class "Default")
      (node (ref "U601") (pin "17") (pinfunction "TXD1_17") (pintype "passive"))
    )
    (net (code "31") (name "/RGMII2_TD2") (class "Default")
      (node (ref "U601") (pin "16") (pinfunction "TXD2_16") (pintype "passive"))
    )
    (net (code "32") (name "/RGMII2_TD4") (class "Default")
      (node (ref "U601") (pin "15") (pinfunction "TXD3_15") (pintype "passive"))
    )
    (net (code "33") (name "/RGMII2_TXC") (class "Default")
      (node (ref "U601") (pin "20") (pinfunction "TXC_20") (pintype "passive"))
    )
    (net (code "34") (name "/RGMII2_TX_CTL") (class "Default")
      (node (ref "U601") (pin "19") (pinfunction "TXCTL_19") (pintype "passive"))
    )
    (net (code "35") (name "/RSET2") (class "Default")
      (node (ref "R605") (pin "1") (pinfunction "1_1") (pintype "passive"))
      (node (ref "U601") (pin "39") (pinfunction "RSET_39") (pintype "passive"))
    )
    (net (code "36") (name "/RXC2{slash}PHYAD1") (class "Default")
      (node (ref "R618") (pin "2") (pinfunction "2_2") (pintype "passive"))
      (node (ref "R619") (pin "1") (pinfunction "1_1") (pintype "passive"))
      (node (ref "U601") (pin "27") (pinfunction "RXC/PHYAD1_27") (pintype "passive"))
    )
    (net (code "37") (name "/RXCTL2{slash}PHYAD2") (class "Default")
      (node (ref "R622") (pin "2") (pinfunction "2_2") (pintype "passive"))
      (node (ref "R623") (pin "1") (pinfunction "1_1") (pintype "passive"))
      (node (ref "U601") (pin "26") (pinfunction "RXCTL/PHYAD2_26") (pintype "passive"))
    )
    (net (code "38") (name "/RXD20{slash}RXDLY") (class "Default")
      (node (ref "R614") (pin "2") (pinfunction "2_2") (pintype "passive"))
      (node (ref "R615") (pin "1") (pinfunction "1_1") (pintype "passive"))
      (node (ref "U601") (pin "25") (pinfunction "RXD0/RXDLY_25") (pintype "passive"))
    )
    (net (code "39") (name "/RXD21{slash}TXDLY") (class "Default")
      (node (ref "R612") (pin "2") (pinfunction "2_2") (pintype "passive"))
      (node (ref "R613") (pin "1") (pinfunction "1_1") (pintype "passive"))
      (node (ref "U601") (pin "24") (pinfunction "RXD1/TXDLY_24") (pintype "passive"))
    )
    (net (code "40") (name "/RXD22{slash}PLLOFF") (class "Default")
      (node (ref "R610") (pin "2") (pinfunction "2_2") (pintype "passive"))
      (node (ref "R611") (pin "1") (pinfunction "1_1") (pintype "passive"))
      (node (ref "U601") (pin "23") (pinfunction "RXD2/PLLOFF_23") (pintype "passive"))
    )
    (net (code "41") (name "/RXD23{slash}PHYAD0") (class "Default")
      (node (ref "R616") (pin "2") (pinfunction "2_2") (pintype "passive"))
      (node (ref "R617") (pin "1") (pinfunction "1_1") (pintype "passive"))
      (node (ref "U601") (pin "22") (pinfunction "RXD3/PHYAD0_22") (pintype "passive"))
    )
    (net (code "42") (name "/TCT2_0") (class "Default")
      (node (ref "C616") (pin "1") (pinfunction "1_1") (pintype "passive"))
      (node (ref "J601") (pin "12") (pinfunction "TRCT1_12") (pintype "passive"))
    )
    (net (code "43") (name "/TCT2_1") (class "Default")
      (node (ref "C617") (pin "1") (pinfunction "1_1") (pintype "passive"))
      (node (ref "J601") (pin "6") (pinfunction "TRCT2_6") (pintype "passive"))
    )
    (net (code "44") (name "/TCT2_2") (class "Default")
      (node (ref "C618") (pin "1") (pinfunction "1_1") (pintype "passive"))
      (node (ref "J601") (pin "1") (pinfunction "TRCT3_1") (pintype "passive"))
    )
    (net (code "45") (name "/TCT2_3") (class "Default")
      (node (ref "C619") (pin "1") (pinfunction "1_1") (pintype "passive"))
      (node (ref "J601") (pin "7") (pinfunction "TRCT4_7") (pintype "passive"))
    )
    (net (code "46") (name "/XTAL_IN_GBE2") (class "Default")
      (node (ref "C621") (pin "1") (pinfunction "1_1") (pintype "passive"))
      (node (ref "U601") (pin "36") (pinfunction "XTAL_IN_36") (pintype "passive"))
      (node (ref "Y601") (pin "1") (pinfunction "1_1") (pintype "passive"))
    )
    (net (code "47") (name "/XTAL_OUT_GBE2") (class "Default")
      (node (ref "C622") (pin "1") (pinfunction "1_1") (pintype "passive"))
      (node (ref "U601") (pin "37") (pinfunction "XTAL_OUT/EXT_CLK_37") (pintype "passive"))
      (node (ref "Y601") (pin "3") (pinfunction "3_3") (pintype "passive"))
    )
    (net (code "48") (name "GND") (class "Default")
      (node (ref "C601") (pin "2") (pinfunction "2_2") (pintype "passive"))
      (node (ref "C602") (pin "2") (pinfunction "2_2") (pintype "passive"))
      (node (ref "C603") (pin "2") (pinfunction "2_2") (pintype "passive"))
      (node (ref "C604") (pin "2") (pinfunction "2_2") (pintype "passive"))
      (node (ref "C605") (pin "2") (pinfunction "2_2") (pintype "passive"))
      (node (ref "C606") (pin "2") (pinfunction "2_2") (pintype "passive"))
      (node (ref "C607") (pin "2") (pinfunction "2_2") (pintype "passive"))
      (node (ref "C608") (pin "2") (pinfunction "2_2") (pintype "passive"))
      (node (ref "C609") (pin "2") (pinfunction "2_2") (pintype "passive"))
      (node (ref "C610") (pin "2") (pinfunction "2_2") (pintype "passive"))
      (node (ref "C611") (pin "2") (pinfunction "2_2") (pintype "passive"))
      (node (ref "C612") (pin "2") (pinfunction "2_2") (pintype "passive"))
      (node (ref "C613") (pin "1") (pinfunction "1_1") (pintype "passive"))
      (node (ref "C614") (pin "1") (pinfunction "1_1") (pintype "passive"))
      (node (ref "C615") (pin "2") (pinfunction "2_2") (pintype "passive"))
      (node (ref "C616") (pin "2") (pinfunction "2_2") (pintype "passive"))
      (node (ref "C617") (pin "2") (pinfunction "2_2") (pintype "passive"))
      (node (ref "C618") (pin "2") (pinfunction "2_2") (pintype "passive"))
      (node (ref "C619") (pin "2") (pinfunction "2_2") (pintype "passive"))
      (node (ref "C620") (pin "2") (pinfunction "2_2") (pintype "passive"))
      (node (ref "C621") (pin "2") (pinfunction "2_2") (pintype "passive"))
      (node (ref "C622") (pin "2") (pinfunction "2_2") (pintype "passive"))
      (node (ref "C623") (pin "1") (pinfunction "1_1") (pintype "passive"))
      (node (ref "D601") (pin "3") (pinfunction "GND1_3") (pintype "passive"))
      (node (ref "D601") (pin "8") (pinfunction "GND1_8") (pintype "passive"))
      (node (ref "D602") (pin "3") (pinfunction "GND1_3") (pintype "passive"))
      (node (ref "D602") (pin "8") (pinfunction "GND1_8") (pintype "passive"))
      (node (ref "R605") (pin "2") (pinfunction "2_2") (pintype "passive"))
      (node (ref "R609") (pin "1") (pinfunction "1_1") (pintype "passive"))
      (node (ref "R610") (pin "1") (pinfunction "1_1") (pintype "passive"))
      (node (ref "R612") (pin "1") (pinfunction "1_1") (pintype "passive"))
      (node (ref "R614") (pin "1") (pinfunction "1_1") (pintype "passive"))
      (node (ref "R616") (pin "1") (pinfunction "1_1") (pintype "passive"))
      (node (ref "R618") (pin "1") (pinfunction "1_1") (pintype "passive"))
      (node (ref "R622") (pin "1") (pinfunction "1_1") (pintype "passive"))
      (node (ref "R626") (pin "1") (pinfunction "1_1") (pintype "passive"))
      (node (ref "R628") (pin "1") (pinfunction "1_1") (pintype "passive"))
      (node (ref "R630") (pin "1") (pinfunction "1_1") (pintype "passive"))
      (node (ref "U601") (pin "41") (pinfunction "EGND_41") (pintype "passive"))
      (node (ref "Y601") (pin "2") (pinfunction "GND_2") (pintype "power_in"))
      (node (ref "Y601") (pin "4") (pinfunction "GND_4") (pintype "power_in"))
    )
    (net (code "49") (name "GND_E") (class "Default")
      (node (ref "C623") (pin "2") (pinfunction "2_2") (pintype "passive"))
      (node (ref "J601") (pin "18") (pinfunction "SHIELD1_18") (pintype "passive"))
      (node (ref "J601") (pin "19") (pinfunction "SHIELD2_19") (pintype "passive"))
      (node (ref "R609") (pin "2") (pinfunction "2_2") (pintype "passive"))
    )
    (net (code "50") (name "Net-(D603-A)") (class "Default")
      (node (ref "D603") (pin "1") (pinfunction "A_1") (pintype "passive"))
      (node (ref "D604") (pin "1") (pinfunction "A_1") (pintype "passive"))
      (node (ref "D605") (pin "1") (pinfunction "A_1") (pintype "passive"))
      (node (ref "Q601") (pin "2") (pinfunction "S_2") (pintype "passive"))
      (node (ref "R624") (pin "1") (pinfunction "1_1") (pintype "passive"))
    )
    (net (code "51") (name "Net-(J601-G_CATODE)") (class "Default")
      (node (ref "J601") (pin "17") (pinfunction "G_CATODE_17") (pintype "passive"))
      (node (ref "R607") (pin "2") (pinfunction "2_2") (pintype "passive"))
    )
    (net (code "52") (name "Net-(J601-O_CATODE)") (class "Default")
      (node (ref "J601") (pin "15") (pinfunction "O_CATODE_15") (pintype "passive"))
      (node (ref "R606") (pin "2") (pinfunction "2_2") (pintype "passive"))
    )
    (net (code "53") (name "Net-(J601-Y_CATODE)") (class "Default")
      (node (ref "J601") (pin "13") (pinfunction "Y_CATODE_13") (pintype "passive"))
      (node (ref "R608") (pin "2") (pinfunction "2_2") (pintype "passive"))
    )
    (net (code "54") (name "PHY2_DVDD3V3") (class "Default")
      (node (ref "C601") (pin "1") (pinfunction "1_1") (pintype "passive"))
      (node (ref "C602") (pin "1") (pinfunction "1_1") (pintype "passive"))
      (node (ref "C620") (pin "1") (pinfunction "1_1") (pintype "passive"))
      (node (ref "FB601") (pin "2") (pinfunction "2_2") (pintype "passive"))
      (node (ref "J601") (pin "14") (pinfunction "Y_ANODE_14") (pintype "passive"))
      (node (ref "J601") (pin "16") (pinfunction "COM_ANODE_16") (pintype "passive"))
      (node (ref "R621") (pin "2") (pinfunction "2_2") (pintype "passive"))
      (node (ref "R625") (pin "2") (pinfunction "2_2") (pintype "passive"))
      (node (ref "R627") (pin "2") (pinfunction "2_2") (pintype "passive"))
      (node (ref "R629") (pin "2") (pinfunction "2_2") (pintype "passive"))
      (node (ref "R631") (pin "2") (pinfunction "2_2") (pintype "passive"))
      (node (ref "U601") (pin "29") (pinfunction "DVDD33_29_29") (pintype "power_in"))
    )
    (net (code "55") (name "PHY2_VDD1V0") (class "Default")
      (node (ref "C614") (pin "2") (pinfunction "2_2") (pintype "passive"))
      (node (ref "C615") (pin "1") (pinfunction "1_1") (pintype "passive"))
      (node (ref "FB602") (pin "2") (pinfunction "2_2") (pintype "passive"))
      (node (ref "FB603") (pin "1") (pinfunction "1_1") (pintype "passive"))
      (node (ref "L601") (pin "2") (pinfunction "2_2") (pintype "passive"))
    )
    (net (code "56") (name "PHY2_VDDIO") (class "Default")
      (node (ref "C605") (pin "1") (pinfunction "1_1") (pintype "passive"))
      (node (ref "C606") (pin "1") (pinfunction "1_1") (pintype "passive"))
      (node (ref "R601") (pin "1") (pinfunction "1_1") (pintype "passive"))
      (node (ref "R611") (pin "2") (pinfunction "2_2") (pintype "passive"))
      (node (ref "R613") (pin "2") (pinfunction "2_2") (pintype "passive"))
      (node (ref "R615") (pin "2") (pinfunction "2_2") (pintype "passive"))
      (node (ref "R617") (pin "2") (pinfunction "2_2") (pintype "passive"))
      (node (ref "R619") (pin "2") (pinfunction "2_2") (pintype "passive"))
      (node (ref "R623") (pin "2") (pinfunction "2_2") (pintype "passive"))
      (node (ref "U601") (pin "28") (pinfunction "DVDD_RG_28") (pintype "power_in"))
    )
  )
)
